# 04_MCU.net
KiCad netlist of a schematic drawn in Altium Designer
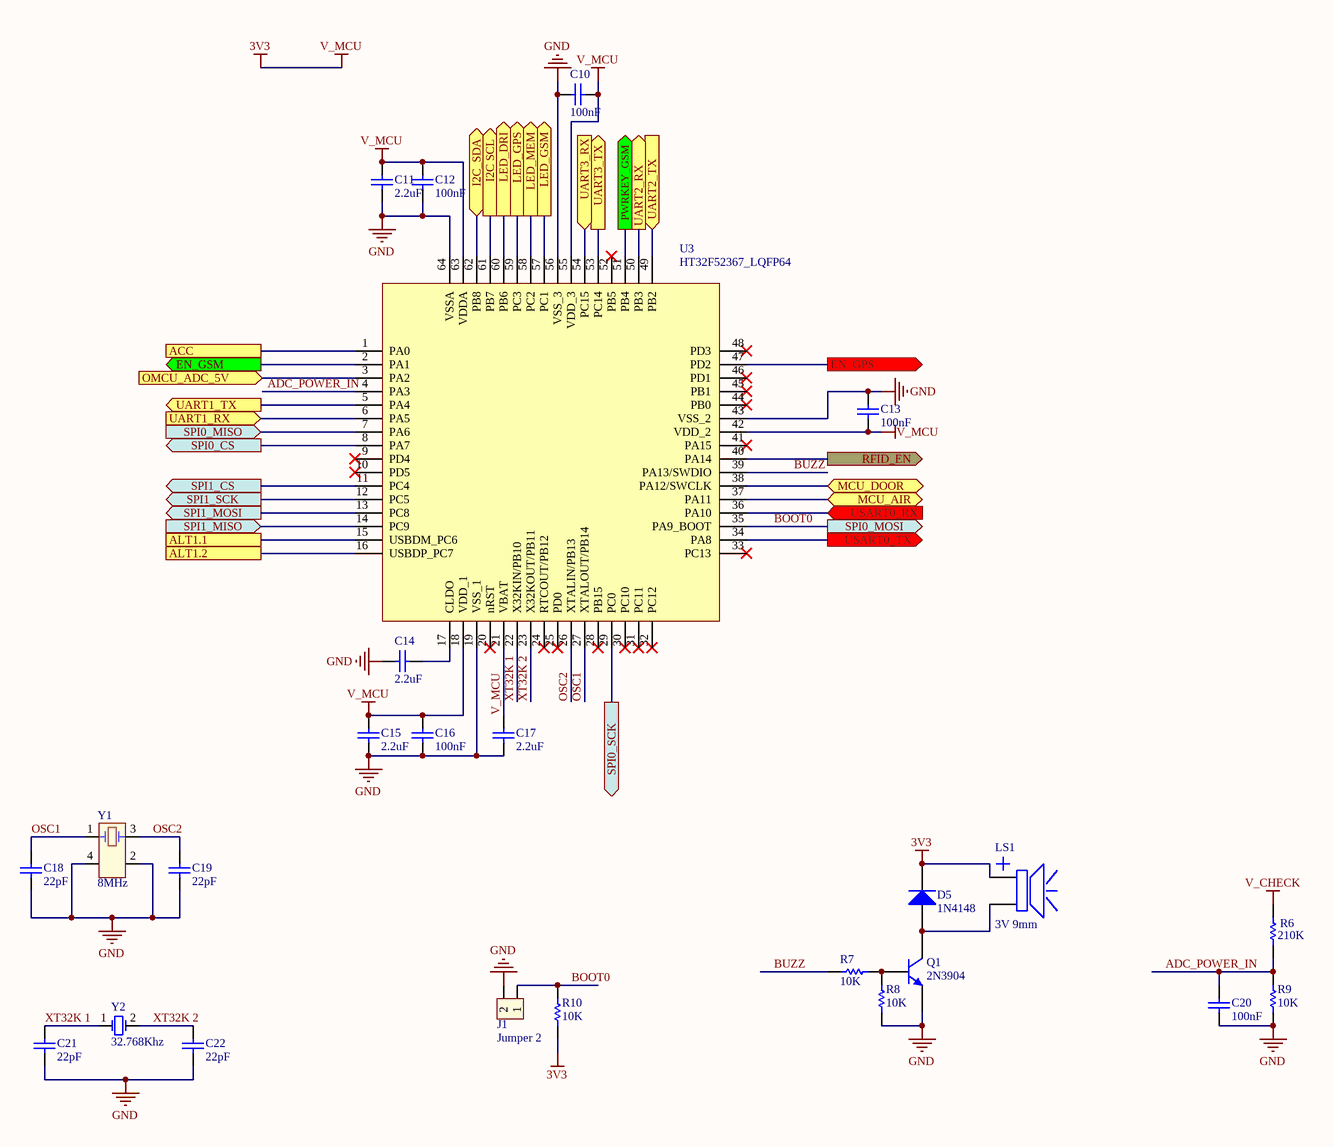
[diagram p0: 04 MCU.SchDoc]

(export (version "E")
  (design (tool "Eeschema 10.0.6"))
  (components
    (comp (ref "C10")
      (value "100nF")
      (footprint "0603 - C")
      (description "CAP CER 100nF 50V C0G/NP0 0603 ±5%")
      (fields (field (name "MPN") "CL10C104JB8NNNC") (field (name "MFR") "SAMSUNG"))
      (libsource (lib "Library_Chip") (part "Cap 0603 100nF"))
    )
    (comp (ref "C11")
      (value "2.2uF")
      (footprint "0603 - C")
      (description "CAP CER 2.2UF 16V X7R 0603")
      (fields (field (name "MPN") "CL10A225KQ8NNNC") (field (name "MFR") "SAMSUNG"))
      (libsource (lib "Library_Chip") (part "Cap 0603 2.2uF"))
    )
    (comp (ref "C12")
      (value "100nF")
      (footprint "0603 - C")
      (description "CAP CER 100nF 50V C0G/NP0 0603 ±5%")
      (fields (field (name "MPN") "CL10C104JB8NNNC") (field (name "MFR") "SAMSUNG"))
      (libsource (lib "Library_Chip") (part "Cap 0603 100nF"))
    )
    (comp (ref "C13")
      (value "100nF")
      (footprint "0603 - C")
      (description "CAP CER 100nF 50V C0G/NP0 0603 ±5%")
      (fields (field (name "MPN") "CL10C104JB8NNNC") (field (name "MFR") "SAMSUNG"))
      (libsource (lib "Library_Chip") (part "Cap 0603 100nF"))
    )
    (comp (ref "C14")
      (value "2.2uF")
      (footprint "0603 - C")
      (description "CAP CER 2.2UF 16V X7R 0603")
      (fields (field (name "MPN") "CL10A225KQ8NNNC") (field (name "MFR") "SAMSUNG"))
      (libsource (lib "Library_Chip") (part "Cap 0603 2.2uF"))
    )
    (comp (ref "C15")
      (value "2.2uF")
      (footprint "0603 - C")
      (description "CAP CER 2.2UF 16V X7R 0603")
      (fields (field (name "MPN") "CL10A225KQ8NNNC") (field (name "MFR") "SAMSUNG"))
      (libsource (lib "Library_Chip") (part "Cap 0603 2.2uF"))
    )
    (comp (ref "C16")
      (value "100nF")
      (footprint "0603 - C")
      (description "CAP CER 100nF 50V C0G/NP0 0603 ±5%")
      (fields (field (name "MPN") "CL10C104JB8NNNC") (field (name "MFR") "SAMSUNG"))
      (libsource (lib "Library_Chip") (part "Cap 0603 100nF"))
    )
    (comp (ref "C17")
      (value "2.2uF")
      (footprint "0603 - C")
      (description "CAP CER 2.2UF 16V X7R 0603")
      (fields (field (name "MPN") "CL10A225KQ8NNNC") (field (name "MFR") "SAMSUNG"))
      (libsource (lib "Library_Chip") (part "Cap 0603 2.2uF"))
    )
    (comp (ref "C18")
      (value "22pF")
      (footprint "0603 - C")
      (description "CAP CER 22PF 50V C0G/NP0 0603")
      (fields (field (name "MPN") "CL10C220JB8NNNC") (field (name "MFR") "SAMSUNG"))
      (libsource (lib "Library_Chip") (part "Cap 0603 22pF"))
    )
    (comp (ref "C19")
      (value "22pF")
      (footprint "0603 - C")
      (description "CAP CER 22PF 50V C0G/NP0 0603")
      (fields (field (name "MPN") "CL10C220JB8NNNC") (field (name "MFR") "SAMSUNG"))
      (libsource (lib "Library_Chip") (part "Cap 0603 22pF"))
    )
    (comp (ref "C20")
      (value "100nF")
      (footprint "0603 - C")
      (description "CAP CER 100nF 50V C0G/NP0 0603 ±5%")
      (fields (field (name "VOLTAGE") "50V") (field (name "MPN") "CL10C104JB8NNNC"))
      (libsource (lib "Library_Chip") (part "Cap 0603 100nF"))
    )
    (comp (ref "C21")
      (value "22pF")
      (footprint "0603 - C")
      (description "CAP CER 22PF 50V C0G/NP0 0603")
      (fields (field (name "MPN") "CL10C220JB8NNNC") (field (name "MFR") "SAMSUNG"))
      (libsource (lib "Library_Chip") (part "Cap 0603 22pF"))
    )
    (comp (ref "C22")
      (value "22pF")
      (footprint "0603 - C")
      (description "CAP CER 22PF 50V C0G/NP0 0603")
      (fields (field (name "MPN") "CL10C220JB8NNNC") (field (name "MFR") "SAMSUNG"))
      (libsource (lib "Library_Chip") (part "Cap 0603 22pF"))
    )
    (comp (ref "D5")
      (value "1N4148")
      (footprint "SOD-123")
      (description "DIODE GEN PURP 100V 300MA SOD123")
      (fields (field (name "MPN") "1N4148W-7-F") (field (name "MFR") "DIODES"))
      (libsource (lib "Library_Chip") (part "Diode 1N4148"))
    )
    (comp (ref "J1")
      (value "Jumper 2")
      (footprint "JP2")
      (description "Jumper 2, 2.54mmx2")
      (libsource (lib "Library_ Connector") (part "JP2"))
    )
    (comp (ref "LS1")
      (value "3V 9mm")
      (footprint "Buzzer")
      (description "Buzzer 9*6mm (D*h)")
      (fields (field (name "MFR") "China") (field (name "MPN") "TMB09A03"))
      (libsource (lib "Library_Chip") (part "Speaker"))
    )
    (comp (ref "Q1")
      (value "2N3904")
      (footprint "SOT23B")
      (description "TRANS NPN 40V 0.2A SOT-23")
      (fields (field (name "MPN") "MMBT3904") (field (name "MFR") "Fairchild"))
      (libsource (lib "Library_Chip") (part "Transistor 2N3904"))
    )
    (comp (ref "R6")
      (value "210K")
      (footprint "0603 - R")
      (description "RES SMD 210K OHM 1% 1/10W 0603")
      (fields (field (name "MFR") "Yageo") (field (name "MPN") "RC0603FR-07210KL"))
      (libsource (lib "Library_Chip") (part "Res 0603 210K"))
    )
    (comp (ref "R7")
      (value "10K")
      (footprint "0603 - R")
      (description "RES SMD 10K OHM 1% 1/10W 0603")
      (fields (field (name "MFR") "Yageo") (field (name "MPN") "RC0603FR-0710KL"))
      (libsource (lib "Library_Chip") (part "Res 0603 10K"))
    )
    (comp (ref "R8")
      (value "10K")
      (footprint "0603 - R")
      (description "RES SMD 10K OHM 1% 1/10W 0603")
      (fields (field (name "MFR") "Yageo") (field (name "MPN") "RC0603FR-0710KL"))
      (libsource (lib "Library_Chip") (part "Res 0603 10K"))
    )
    (comp (ref "R9")
      (value "10K")
      (footprint "0603 - R")
      (description "RES SMD 10K OHM 1% 1/10W 0603")
      (fields (field (name "MFR") "Yageo") (field (name "MPN") "RC0603FR-0710KL"))
      (libsource (lib "Library_Chip") (part "Res 0603 10K"))
    )
    (comp (ref "R10")
      (value "10K")
      (footprint "0603 - R")
      (description "RES SMD 10K OHM 1% 1/10W 0603")
      (fields (field (name "MFR") "Yageo") (field (name "MPN") "RC0603FR-0710KL"))
      (libsource (lib "Library_Chip") (part "Res 0603 10K"))
    )
    (comp (ref "U3")
      (value "HT32F52367_LQFP64")
      (footprint "HT_LQFP64")
      (libsource (lib "Holtek") (part "HT32F52367_LQFP64"))
    )
    (comp (ref "Y1")
      (value "8MHz")
      (footprint "Crystal 3225")
      (description "CRYSTAL 8.0MHZ 10PF SMD")
      (fields (field (name "MFR") "Taisaw") (field (name "MPN") "TZ3313B"))
      (libsource (lib "Library_Chip") (part "XTAL 8MHz 3225"))
    )
    (comp (ref "Y2")
      (value "32.768Khz")
      (footprint "Crystal 3215")
      (description "CRYSTAL 32.7680KHZ 12.5PF SMD")
      (fields (field (name "MFR") "Abracon LLC") (field (name "MPN") "ABS07-32.768KHZ-T"))
      (libsource (lib "Library_Chip") (part "XTAL ABS07-32.768KHz"))
    )
  )
  (nets
    (net (code "1") (name "/ACC") (class "Default")
      (node (ref "U3") (pin "1") (pinfunction "PA0_1") (pintype "passive"))
    )
    (net (code "2") (name "/ADC_POWER_IN") (class "Default")
      (node (ref "C20") (pin "2") (pinfunction "2_2") (pintype "passive"))
      (node (ref "R6") (pin "1") (pinfunction "1_1") (pintype "passive"))
      (node (ref "R9") (pin "2") (pinfunction "2_2") (pintype "passive"))
      (node (ref "U3") (pin "4") (pinfunction "PA3_4") (pintype "passive"))
    )
    (net (code "3") (name "/ALT1.1") (class "Default")
      (node (ref "U3") (pin "15") (pinfunction "USBDM_PC6_15") (pintype "passive"))
    )
    (net (code "4") (name "/ALT1.2") (class "Default")
      (node (ref "U3") (pin "16") (pinfunction "USBDP_PC7_16") (pintype "passive"))
    )
    (net (code "5") (name "/BOOT0") (class "Default")
      (node (ref "J1") (pin "1") (pinfunction "1_1") (pintype "passive"))
      (node (ref "R10") (pin "2") (pinfunction "2_2") (pintype "passive"))
      (node (ref "U3") (pin "35") (pinfunction "PA9_BOOT_35") (pintype "passive"))
    )
    (net (code "6") (name "/BUZZ") (class "Default")
      (node (ref "R7") (pin "2") (pinfunction "2_2") (pintype "passive"))
      (node (ref "U3") (pin "39") (pinfunction "PA13/SWDIO_39") (pintype "passive"))
    )
    (net (code "7") (name "/EN_GPS") (class "Default")
      (node (ref "U3") (pin "47") (pinfunction "PD2_47") (pintype "passive"))
    )
    (net (code "8") (name "/EN_GSM") (class "Default")
      (node (ref "U3") (pin "2") (pinfunction "PA1_2") (pintype "passive"))
    )
    (net (code "9") (name "/I2C SCL") (class "Default")
      (node (ref "U3") (pin "61") (pinfunction "PB7_61") (pintype "passive"))
    )
    (net (code "10") (name "/I2C_SDA") (class "Default")
      (node (ref "U3") (pin "62") (pinfunction "PB8_62") (pintype "passive"))
    )
    (net (code "11") (name "/LED_DRI") (class "Default")
      (node (ref "U3") (pin "60") (pinfunction "PB6_60") (pintype "passive"))
    )
    (net (code "12") (name "/LED_GPS") (class "Default")
      (node (ref "U3") (pin "59") (pinfunction "PC3_59") (pintype "passive"))
    )
    (net (code "13") (name "/LED_GSM") (class "Default")
      (node (ref "U3") (pin "57") (pinfunction "PC1_57") (pintype "passive"))
    )
    (net (code "14") (name "/LED_MEM") (class "Default")
      (node (ref "U3") (pin "58") (pinfunction "PC2_58") (pintype "passive"))
    )
    (net (code "15") (name "/MCU_AIR") (class "Default")
      (node (ref "U3") (pin "37") (pinfunction "PA11_37") (pintype "passive"))
    )
    (net (code "16") (name "/MCU_DOOR") (class "Default")
      (node (ref "U3") (pin "38") (pinfunction "PA12/SWCLK_38") (pintype "passive"))
    )
    (net (code "17") (name "/OMCU_ADC_5V") (class "Default")
      (node (ref "U3") (pin "3") (pinfunction "PA2_3") (pintype "passive"))
    )
    (net (code "18") (name "/OSC1") (class "Default")
      (node (ref "C18") (pin "2") (pinfunction "2_2") (pintype "passive"))
      (node (ref "U3") (pin "27") (pinfunction "XTALOUT/PB14_27") (pintype "passive"))
      (node (ref "Y1") (pin "1") (pinfunction "OSC1_1") (pintype "passive"))
    )
    (net (code "19") (name "/OSC2") (class "Default")
      (node (ref "C19") (pin "2") (pinfunction "2_2") (pintype "passive"))
      (node (ref "U3") (pin "26") (pinfunction "XTALIN/PB13_26") (pintype "passive"))
      (node (ref "Y1") (pin "3") (pinfunction "OSC2_3") (pintype "passive"))
    )
    (net (code "20") (name "/PWRKEY_GSM") (class "Default")
      (node (ref "U3") (pin "51") (pinfunction "PB4_51") (pintype "passive"))
    )
    (net (code "21") (name "/RFID_EN") (class "Default")
      (node (ref "U3") (pin "40") (pinfunction "PA14_40") (pintype "passive"))
    )
    (net (code "22") (name "/SPI0_CS") (class "Default")
      (node (ref "U3") (pin "8") (pinfunction "PA7_8") (pintype "passive"))
    )
    (net (code "23") (name "/SPI0_MISO") (class "Default")
      (node (ref "U3") (pin "7") (pinfunction "PA6_7") (pintype "passive"))
    )
    (net (code "24") (name "/SPI0_SCK") (class "Default")
      (node (ref "U3") (pin "29") (pinfunction "PC0_29") (pintype "passive"))
    )
    (net (code "25") (name "/SPI1_CS") (class "Default")
      (node (ref "U3") (pin "11") (pinfunction "PC4_11") (pintype "passive"))
    )
    (net (code "26") (name "/SPI1_MISO") (class "Default")
      (node (ref "U3") (pin "14") (pinfunction "PC9_14") (pintype "passive"))
    )
    (net (code "27") (name "/SPI1_MOSI") (class "Default")
      (node (ref "U3") (pin "13") (pinfunction "PC8_13") (pintype "passive"))
    )
    (net (code "28") (name "/SPI1_SCK") (class "Default")
      (node (ref "U3") (pin "12") (pinfunction "PC5_12") (pintype "passive"))
    )
    (net (code "29") (name "/UART1_RX") (class "Default")
      (node (ref "U3") (pin "6") (pinfunction "PA5_6") (pintype "passive"))
    )
    (net (code "30") (name "/UART1_TX") (class "Default")
      (node (ref "U3") (pin "5") (pinfunction "PA4_5") (pintype "passive"))
    )
    (net (code "31") (name "/UART2_RX") (class "Default")
      (node (ref "U3") (pin "50") (pinfunction "PB3_50") (pintype "passive"))
    )
    (net (code "32") (name "/UART2_TX") (class "Default")
      (node (ref "U3") (pin "49") (pinfunction "PB2_49") (pintype "passive"))
    )
    (net (code "33") (name "/UART3_RX") (class "Default")
      (node (ref "U3") (pin "54") (pinfunction "PC15_54") (pintype "passive"))
    )
    (net (code "34") (name "/UART3_TX") (class "Default")
      (node (ref "U3") (pin "53") (pinfunction "PC14_53") (pintype "passive"))
    )
    (net (code "35") (name "/USART0_RX") (class "Default")
      (node (ref "U3") (pin "36") (pinfunction "PA10_36") (pintype "passive"))
    )
    (net (code "36") (name "/USART0_TX") (class "Default")
      (node (ref "U3") (pin "34") (pinfunction "PA8_34") (pintype "passive"))
    )
    (net (code "37") (name "/XT32K 1") (class "Default")
      (node (ref "C21") (pin "2") (pinfunction "2_2") (pintype "passive"))
      (node (ref "U3") (pin "22") (pinfunction "X32KIN/PB10_22") (pintype "passive"))
      (node (ref "Y2") (pin "1") (pinfunction "OSC1_1") (pintype "passive"))
    )
    (net (code "38") (name "/XT32K 2") (class "Default")
      (node (ref "C22") (pin "2") (pinfunction "2_2") (pintype "passive"))
      (node (ref "U3") (pin "23") (pinfunction "X32KOUT/PB11_23") (pintype "passive"))
      (node (ref "Y2") (pin "2") (pinfunction "GND_2") (pintype "passive"))
    )
    (net (code "39") (name "3V3") (class "Default")
      (node (ref "C10") (pin "2") (pinfunction "2_2") (pintype "passive"))
      (node (ref "C11") (pin "2") (pinfunction "2_2") (pintype "passive"))
      (node (ref "C12") (pin "2") (pinfunction "2_2") (pintype "passive"))
      (node (ref "C13") (pin "1") (pinfunction "1_1") (pintype "passive"))
      (node (ref "C15") (pin "2") (pinfunction "2_2") (pintype "passive"))
      (node (ref "C16") (pin "2") (pinfunction "2_2") (pintype "passive"))
      (node (ref "C17") (pin "2") (pinfunction "2_2") (pintype "passive"))
      (node (ref "D5") (pin "2") (pinfunction "K_2") (pintype "passive"))
      (node (ref "LS1") (pin "1") (pinfunction "1_1") (pintype "passive"))
      (node (ref "R10") (pin "1") (pinfunction "1_1") (pintype "passive"))
      (node (ref "U3") (pin "18") (pinfunction "VDD_1_18") (pintype "passive"))
      (node (ref "U3") (pin "21") (pinfunction "VBAT_21") (pintype "passive"))
      (node (ref "U3") (pin "42") (pinfunction "VDD_2_42") (pintype "passive"))
      (node (ref "U3") (pin "55") (pinfunction "VDD_3_55") (pintype "passive"))
      (node (ref "U3") (pin "63") (pinfunction "VDDA_63") (pintype "passive"))
    )
    (net (code "40") (name "GND") (class "Default")
      (node (ref "C10") (pin "1") (pinfunction "1_1") (pintype "passive"))
      (node (ref "C11") (pin "1") (pinfunction "1_1") (pintype "passive"))
      (node (ref "C12") (pin "1") (pinfunction "1_1") (pintype "passive"))
      (node (ref "C13") (pin "2") (pinfunction "2_2") (pintype "passive"))
      (node (ref "C14") (pin "1") (pinfunction "1_1") (pintype "passive"))
      (node (ref "C15") (pin "1") (pinfunction "1_1") (pintype "passive"))
      (node (ref "C16") (pin "1") (pinfunction "1_1") (pintype "passive"))
      (node (ref "C17") (pin "1") (pinfunction "1_1") (pintype "passive"))
      (node (ref "C18") (pin "1") (pinfunction "1_1") (pintype "passive"))
      (node (ref "C19") (pin "1") (pinfunction "1_1") (pintype "passive"))
      (node (ref "C20") (pin "1") (pinfunction "1_1") (pintype "passive"))
      (node (ref "C21") (pin "1") (pinfunction "1_1") (pintype "passive"))
      (node (ref "C22") (pin "1") (pinfunction "1_1") (pintype "passive"))
      (node (ref "J1") (pin "2") (pinfunction "2_2") (pintype "passive"))
      (node (ref "Q1") (pin "2") (pinfunction "E_2") (pintype "passive"))
      (node (ref "R8") (pin "1") (pinfunction "1_1") (pintype "passive"))
      (node (ref "R9") (pin "1") (pinfunction "1_1") (pintype "passive"))
      (node (ref "U3") (pin "19") (pinfunction "VSS_1_19") (pintype "passive"))
      (node (ref "U3") (pin "43") (pinfunction "VSS_2_43") (pintype "passive"))
      (node (ref "U3") (pin "56") (pinfunction "VSS_3_56") (pintype "passive"))
      (node (ref "U3") (pin "64") (pinfunction "VSSA_64") (pintype "passive"))
      (node (ref "Y1") (pin "2") (pinfunction "GND_2") (pintype "power_in"))
      (node (ref "Y1") (pin "4") (pinfunction "GND_4") (pintype "power_in"))
    )
    (net (code "41") (name "Net-(D5-A)") (class "Default")
      (node (ref "D5") (pin "1") (pinfunction "A_1") (pintype "passive"))
      (node (ref "LS1") (pin "2") (pinfunction "2_2") (pintype "passive"))
      (node (ref "Q1") (pin "3") (pinfunction "C_3") (pintype "passive"))
    )
    (net (code "42") (name "Net-(Q1-B)") (class "Default")
      (node (ref "Q1") (pin "1") (pinfunction "B_1") (pintype "passive"))
      (node (ref "R7") (pin "1") (pinfunction "1_1") (pintype "passive"))
      (node (ref "R8") (pin "2") (pinfunction "2_2") (pintype "passive"))
    )
    (net (code "43") (name "Net-(U3-CLDO)") (class "Default")
      (node (ref "C14") (pin "2") (pinfunction "2_2") (pintype "passive"))
      (node (ref "U3") (pin "17") (pinfunction "CLDO_17") (pintype "passive"))
    )
    (net (code "44") (name "V_CHECK") (class "Default")
      (node (ref "R6") (pin "2") (pinfunction "2_2") (pintype "passive"))
    )
    (net (code "45") (name "unconnected-(U3-PA15-Pad41)") (class "Default")
      (node (ref "U3") (pin "41") (pinfunction "PA15_41") (pintype "passive+no_connect"))
    )
    (net (code "46") (name "unconnected-(U3-PB0-Pad44)") (class "Default")
      (node (ref "U3") (pin "44") (pinfunction "PB0_44") (pintype "passive+no_connect"))
    )
    (net (code "47") (name "unconnected-(U3-PB1-Pad45)") (class "Default")
      (node (ref "U3") (pin "45") (pinfunction "PB1_45") (pintype "passive+no_connect"))
    )
    (net (code "48") (name "unconnected-(U3-PB5-Pad52)") (class "Default")
      (node (ref "U3") (pin "52") (pinfunction "PB5_52") (pintype "passive+no_connect"))
    )
    (net (code "49") (name "unconnected-(U3-PB15-Pad28)") (class "Default")
      (node (ref "U3") (pin "28") (pinfunction "PB15_28") (pintype "passive+no_connect"))
    )
    (net (code "50") (name "unconnected-(U3-PC10-Pad30)") (class "Default")
      (node (ref "U3") (pin "30") (pinfunction "PC10_30") (pintype "passive+no_connect"))
    )
    (net (code "51") (name "unconnected-(U3-PC11-Pad31)") (class "Default")
      (node (ref "U3") (pin "31") (pinfunction "PC11_31") (pintype "passive+no_connect"))
    )
    (net (code "52") (name "unconnected-(U3-PC12-Pad32)") (class "Default")
      (node (ref "U3") (pin "32") (pinfunction "PC12_32") (pintype "passive+no_connect"))
    )
    (net (code "53") (name "unconnected-(U3-PC13-Pad33)") (class "Default")
      (node (ref "U3") (pin "33") (pinfunction "PC13_33") (pintype "passive+no_connect"))
    )
    (net (code "54") (name "unconnected-(U3-PD0-Pad25)") (class "Default")
      (node (ref "U3") (pin "25") (pinfunction "PD0_25") (pintype "passive+no_connect"))
    )
    (net (code "55") (name "unconnected-(U3-PD1-Pad46)") (class "Default")
      (node (ref "U3") (pin "46") (pinfunction "PD1_46") (pintype "passive+no_connect"))
    )
    (net (code "56") (name "unconnected-(U3-PD3-Pad48)") (class "Default")
      (node (ref "U3") (pin "48") (pinfunction "PD3_48") (pintype "passive+no_connect"))
    )
    (net (code "57") (name "unconnected-(U3-PD4-Pad9)") (class "Default")
      (node (ref "U3") (pin "9") (pinfunction "PD4_9") (pintype "passive+no_connect"))
    )
    (net (code "58") (name "unconnected-(U3-PD5-Pad10)") (class "Default")
      (node (ref "U3") (pin "10") (pinfunction "PD5_10") (pintype "passive+no_connect"))
    )
    (net (code "59") (name "unconnected-(U3-RTCOUT{slash}PB12-Pad24)") (class "Default")
      (node (ref "U3") (pin "24") (pinfunction "RTCOUT/PB12_24") (pintype "passive+no_connect"))
    )
    (net (code "60") (name "unconnected-(U3-nRST-Pad20)") (class "Default")
      (node (ref "U3") (pin "20") (pinfunction "nRST_20") (pintype "passive+no_connect"))
    )
  )
)
